# USB-Serial.net
KiCad netlist of a schematic drawn in Altium Designer
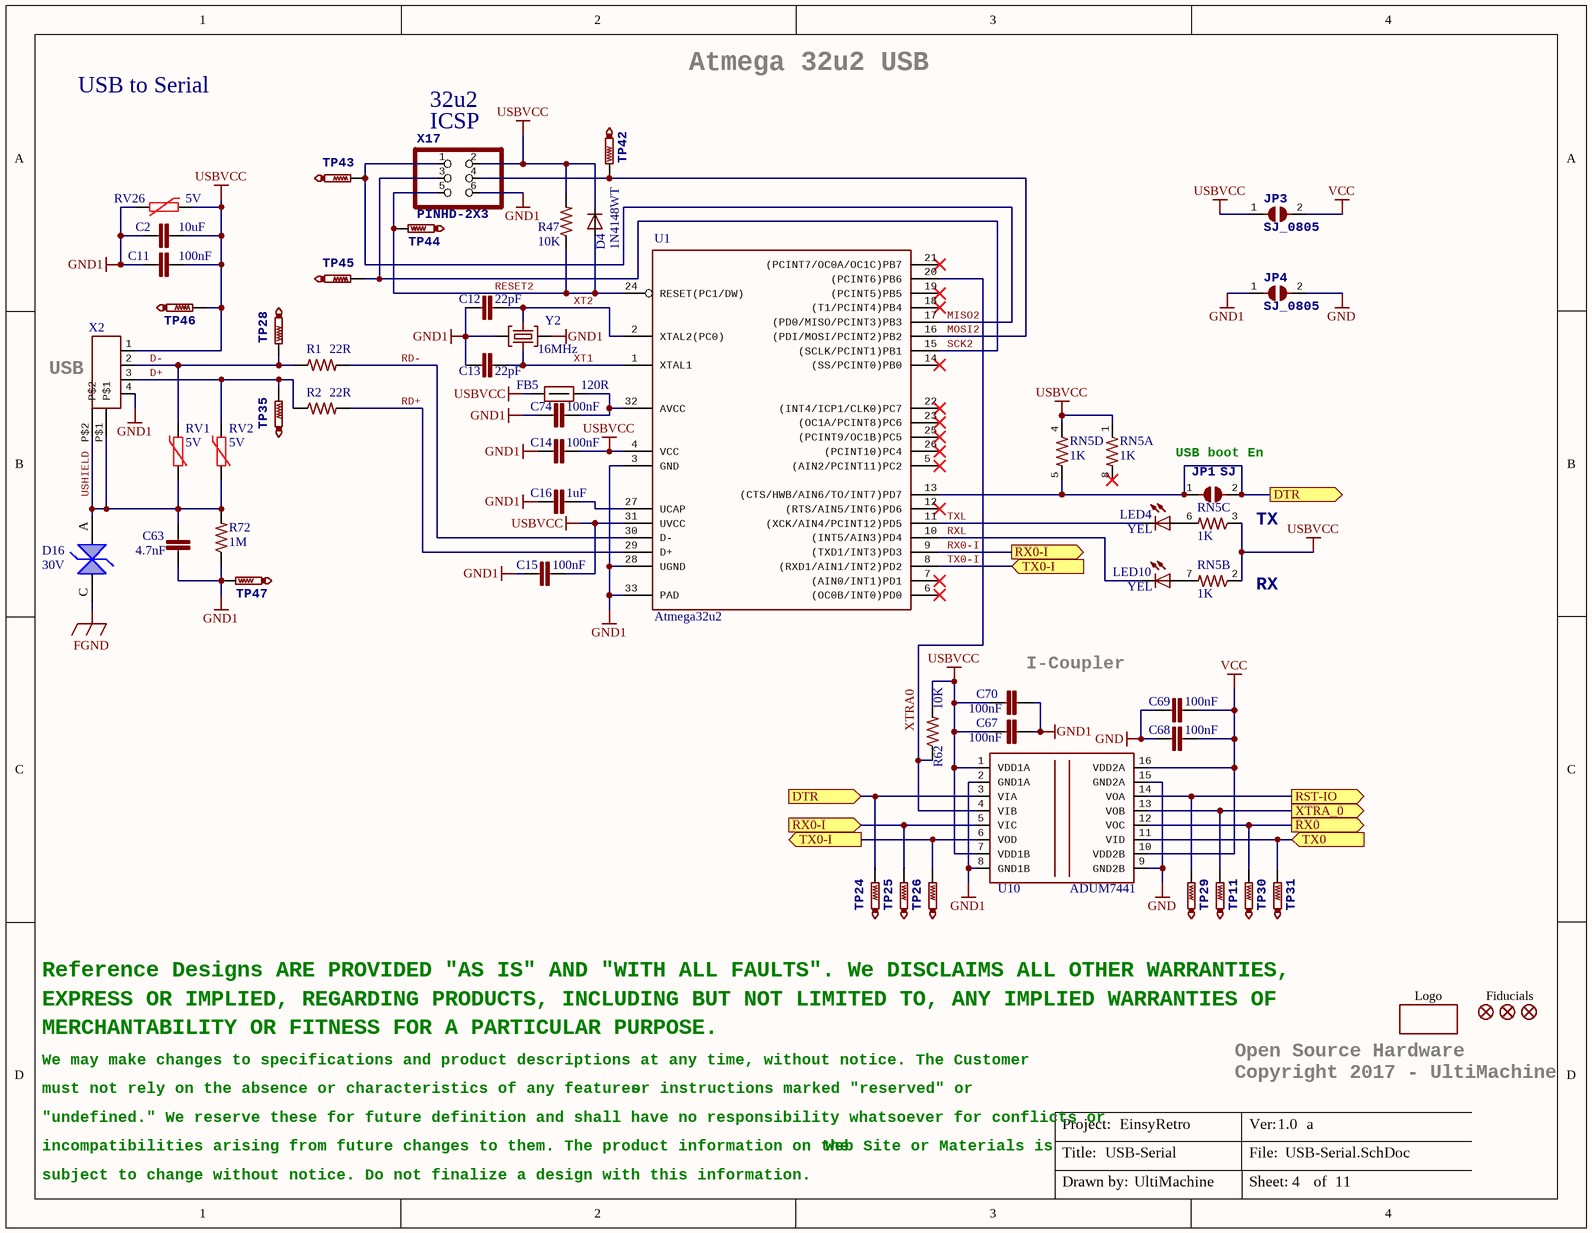
[diagram p0: USB-Serial.SchDoc]

(export (version "E")
  (design (tool "Eeschema 10.0.6"))
  (components
    (comp (ref "C2")
      (value "10uF")
      (footprint "C0805")
      (description "CAP CER 0805 10uF 10V 10% X5R")
      (fields (field (name "MANUFACTURER") "Kemet") (field (name "TOLERANCE") "+/- 10%"))
      (libsource (lib "3Delight") (part "C0805C106K8PACTU"))
    )
    (comp (ref "C11")
      (value "100nF")
      (footprint "C0402")
      (description "CAP CER 0402 100nF 16V 10% X7R")
      (fields (field (name "MANUFACTURER") "Murata") (field (name "TOLERANCE") "+/- 10%"))
      (libsource (lib "") (part "GRM155R71C104KA88D_1"))
    )
    (comp (ref "C12")
      (value "22pF")
      (footprint "C0402")
      (description "CAP CER 0402 22pF 50V 5% C0G")
      (fields (field (name "MANUFACTURER") "AVX") (field (name "PART") "22pF 50V"))
      (libsource (lib "3Delight") (part "04025A220JAT2A"))
    )
    (comp (ref "C13")
      (value "22pF")
      (footprint "C0402")
      (description "CAP CER 0402 22pF 50V 5% C0G")
      (fields (field (name "MANUFACTURER") "AVX") (field (name "PART") "22pF 50V"))
      (libsource (lib "3Delight") (part "04025A220JAT2A"))
    )
    (comp (ref "C14")
      (value "100nF")
      (footprint "C0402")
      (description "CAP CER 0402 100nF 16V 10% X7R")
      (fields (field (name "MANUFACTURER") "Murata") (field (name "TOLERANCE") "+/- 10%"))
      (libsource (lib "") (part "GRM155R71C104KA88D_1"))
    )
    (comp (ref "C15")
      (value "100nF")
      (footprint "C0402")
      (description "CAP CER 0402 100nF 16V 10% X7R")
      (fields (field (name "MANUFACTURER") "Murata") (field (name "TOLERANCE") "+/- 10%"))
      (libsource (lib "") (part "GRM155R71C104KA88D_1"))
    )
    (comp (ref "C16")
      (value "1uF")
      (footprint "C0402")
      (description "CAP CER 0402 1uF 6.3V 10% X5R")
      (fields (field (name "MANUFACTURER") "Murata") (field (name "TOLERANCE") "+/- 10%"))
      (libsource (lib "3Delight") (part "GRM155R60J105KE19D"))
    )
    (comp (ref "C63")
      (value "4.7nF")
      (footprint "C0402")
      (description "CAP CER 0402 4.7nF 25V 10% X7R")
      (fields (field (name "MANUFACTURER") "YAGEO") (field (name "TOLERANCE") "+/- 10%"))
      (libsource (lib "3Delight") (part "CC0402KRX7R8BB472"))
    )
    (comp (ref "C67")
      (value "100nF")
      (footprint "C0402")
      (description "CAP CER 0402 100nF 16V 10% X7R")
      (fields (field (name "MANUFACTURER") "Murata") (field (name "TOLERANCE") "+/- 10%"))
      (libsource (lib "") (part "GRM155R71C104KA88D_1"))
    )
    (comp (ref "C68")
      (value "100nF")
      (footprint "C0402")
      (description "CAP CER 0402 100nF 16V 10% X7R")
      (fields (field (name "MANUFACTURER") "Murata") (field (name "TOLERANCE") "+/- 10%"))
      (libsource (lib "3Delight") (part "GRM155R71C104KA88D"))
    )
    (comp (ref "C69")
      (value "100nF")
      (footprint "C0402")
      (description "CAP CER 0402 100nF 16V 10% X7R")
      (fields (field (name "MANUFACTURER") "Murata") (field (name "TOLERANCE") "+/- 10%"))
      (libsource (lib "") (part "GRM155R71C104KA88D_1"))
    )
    (comp (ref "C70")
      (value "100nF")
      (footprint "C0402")
      (description "CAP CER 0402 100nF 16V 10% X7R")
      (fields (field (name "MANUFACTURER") "Murata") (field (name "TOLERANCE") "+/- 10%"))
      (libsource (lib "3Delight") (part "GRM155R71C104KA88D"))
    )
    (comp (ref "C74")
      (value "100nF")
      (footprint "C0402")
      (description "CAP CER 0402 100nF 16V 10% X7R")
      (fields (field (name "MANUFACTURER") "Murata") (field (name "TOLERANCE") "+/- 10%"))
      (libsource (lib "") (part "GRM155R71C104KA88D_1"))
    )
    (comp (ref "D4")
      (value "1N4148WT")
      (footprint "SOD523")
      (description "DIODE SOD523")
      (fields (field (name "MANUFACTURER") "Fairchild") (field (name "TOLERANCE") "NA"))
      (libsource (lib "3Delight") (part "1N4148WT"))
    )
    (comp (ref "D16")
      (value "30V")
      (footprint "SOD323-R")
      (description "DIODE TVS")
      (fields (field (name "MANUFACTURER") "Rohm") (field (name "TOLERANCE") "NA"))
      (libsource (lib "3Delight") (part "RSB39VTE-17"))
    )
    (comp (ref "FB5")
      (value "120R")
      (footprint "FB0603")
      (description "FERRITE BEAD 120 OHM 0603 1LN")
      (fields (field (name "MANUFACTURER") "Samsung") (field (name "PART") "FERRITE 120R 3A 0603"))
      (libsource (lib "3Delight") (part "FERRITE 220R 2.5A 0603"))
    )
    (comp (ref "FID1")
      (value "FIDUCIAL")
      (footprint "FIDUCIAL-1X2")
      (description "Fiducial")
      (libsource (lib "3Delight") (part "FIDUCIAL"))
    )
    (comp (ref "FID2")
      (value "FIDUCIAL")
      (footprint "FIDUCIAL-1X2")
      (description "Fiducial")
      (libsource (lib "3Delight") (part "FIDUCIAL"))
    )
    (comp (ref "FID3")
      (value "FIDUCIAL")
      (footprint "FIDUCIAL-1X2")
      (description "Fiducial")
      (libsource (lib "3Delight") (part "FIDUCIAL"))
    )
    (comp (ref "JP1")
      (value "SJ")
      (footprint "SJ")
      (description "SMD solder jumper")
      (libsource (lib "3Delight") (part "SJ"))
    )
    (comp (ref "JP3")
      (value "SJ_0805")
      (footprint "R0805")
      (description "SMD solder jumper")
      (fields (field (name "PUBLISHER") "UltiMachine"))
      (libsource (lib "3Delight") (part "SJ_0805"))
    )
    (comp (ref "JP4")
      (value "SJ_0805")
      (footprint "R0805")
      (description "SMD solder jumper")
      (fields (field (name "PUBLISHER") "UltiMachine"))
      (libsource (lib "3Delight") (part "SJ_0805"))
    )
    (comp (ref "LED4")
      (value "YEL")
      (footprint "LED2012120")
      (description "LED 0805 Yellow")
      (fields (field (name "MANUFACTURER") "Dialight") (field (name "TOLERANCE") "NA"))
      (libsource (lib "3Delight") (part "5988140107F"))
    )
    (comp (ref "LED10")
      (value "YEL")
      (footprint "LED2012120")
      (description "LED 0805 Yellow")
      (fields (field (name "MANUFACTURER") "Dialight") (field (name "TOLERANCE") "NA"))
      (libsource (lib "3Delight") (part "5988140107F"))
    )
    (comp (ref "LOGO1")
      (value "OSHW_LOGO_8MILX0150-NT")
      (footprint "OSHW_8X150_NOTEXT")
      (libsource (lib "3Delight") (part "OSHW_LOGO_8MILX0150-NT"))
    )
    (comp (ref "R1")
      (value "22R")
      (footprint "R0402")
      (description "RES 0402 22r 62.5mW 1%")
      (fields (field (name "MANUFACTURER") "Yageo") (field (name "TOLERANCE") "+/- 1%"))
      (libsource (lib "3Delight") (part "RC0402FR-0722RL"))
    )
    (comp (ref "R2")
      (value "22R")
      (footprint "R0402")
      (description "RES 0402 22r 62.5mW 1%")
      (fields (field (name "MANUFACTURER") "Yageo") (field (name "TOLERANCE") "+/- 1%"))
      (libsource (lib "3Delight") (part "RC0402FR-0722RL"))
    )
    (comp (ref "R47")
      (value "10K")
      (footprint "R0402")
      (description "RES SMD 10K OHM 1% 1/16W 0402")
      (fields (field (name "MANUFACTURER") "Yageo") (field (name "PART") "10k 1% 0402"))
      (libsource (lib "3Delight") (part "RC0402FR-0710KP"))
    )
    (comp (ref "R62")
      (value "10K")
      (footprint "R0402")
      (description "RES SMD 10K OHM 1% 1/16W 0402")
      (fields (field (name "MANUFACTURER") "Yageo") (field (name "PART") "10k 1% 0402"))
      (libsource (lib "3Delight") (part "RC0402FR-0710KP"))
    )
    (comp (ref "R72")
      (value "1M")
      (footprint "R0402")
      (description "RES 0402 1M 100mW 5%")
      (fields (field (name "MANUFACTURER") "Panasonic") (field (name "TOLERANCE") "+/- 1%"))
      (libsource (lib "3Delight") (part "ERJ2GEJ105X"))
    )
    (comp (ref "RN5")
      (value "1K")
      (footprint "CAY16")
      (description "RES ARRAY 4 RES 1K 1206 62.5mW 5%")
      (fields (field (name "MANUFACTURER") "Bourns") (field (name "TOLERANCE") "+/- 5%"))
      (libsource (lib "3Delight") (part "CAY16-102J4LF"))
    )
    (comp (ref "RV1")
      (value "5V")
      (footprint "R0603")
      (description "VAR 0603 5V")
      (fields (field (name "MANUFACTURER") "YAGEO") (field (name "PART") "5VDC"))
      (libsource (lib "3Delight") (part "CG0603MLC-05E"))
    )
    (comp (ref "RV2")
      (value "5V")
      (footprint "R0603")
      (description "VAR 0603 5V")
      (fields (field (name "MANUFACTURER") "YAGEO") (field (name "PART") "5VDC"))
      (libsource (lib "3Delight") (part "CG0603MLC-05E"))
    )
    (comp (ref "RV26")
      (value "5V")
      (footprint "R0603")
      (description "VAR 0603 5V")
      (fields (field (name "MANUFACTURER") "YAGEO") (field (name "PART") "5VDC"))
      (libsource (lib "3Delight") (part "CG0603MLC-05E"))
    )
    (comp (ref "TP11")
      (value "TestPoint")
      (footprint "TP1-27")
      (description "Test Point")
      (libsource (lib "") (part "TestPoint_1"))
    )
    (comp (ref "TP24")
      (value "TestPoint")
      (footprint "TP1-27")
      (description "Test Point")
      (libsource (lib "") (part "TestPoint_1"))
    )
    (comp (ref "TP25")
      (value "TestPoint")
      (footprint "TP1-27")
      (description "Test Point")
      (libsource (lib "") (part "TestPoint_1"))
    )
    (comp (ref "TP26")
      (value "TestPoint")
      (footprint "TP1-27")
      (description "Test Point")
      (libsource (lib "") (part "TestPoint_1"))
    )
    (comp (ref "TP28")
      (value "TestPoint")
      (footprint "TP1-27")
      (description "Test Point")
      (libsource (lib "") (part "TestPoint_2"))
    )
    (comp (ref "TP29")
      (value "TestPoint")
      (footprint "TP1-27")
      (description "Test Point")
      (libsource (lib "") (part "TestPoint_1"))
    )
    (comp (ref "TP30")
      (value "TestPoint")
      (footprint "TP1-27")
      (description "Test Point")
      (libsource (lib "") (part "TestPoint_1"))
    )
    (comp (ref "TP31")
      (value "TestPoint")
      (footprint "TP1-27")
      (description "Test Point")
      (libsource (lib "") (part "TestPoint_1"))
    )
    (comp (ref "TP35")
      (value "TestPoint")
      (footprint "TP1-27")
      (description "Test Point")
      (libsource (lib "") (part "TestPoint_1"))
    )
    (comp (ref "TP42")
      (value "TestPoint")
      (footprint "TP1-27")
      (description "Test Point")
      (libsource (lib "") (part "TestPoint_2"))
    )
    (comp (ref "TP43")
      (value "TestPoint")
      (footprint "TP1-27")
      (description "Test Point")
      (libsource (lib "3Delight") (part "TestPoint"))
    )
    (comp (ref "TP44")
      (value "TestPoint")
      (footprint "TP1-27")
      (description "Test Point")
      (libsource (lib "") (part "TestPoint_3"))
    )
    (comp (ref "TP45")
      (value "TestPoint")
      (footprint "TP1-27")
      (description "Test Point")
      (libsource (lib "3Delight") (part "TestPoint"))
    )
    (comp (ref "TP46")
      (value "TestPoint")
      (footprint "TP1-27")
      (description "Test Point")
      (libsource (lib "3Delight") (part "TestPoint"))
    )
    (comp (ref "TP47")
      (value "TestPoint")
      (footprint "TP1-27")
      (description "Test Point")
      (libsource (lib "") (part "TestPoint_3"))
    )
    (comp (ref "U1")
      (value "Atmega32u2")
      (footprint "QFN32_050050")
      (fields
        (field (name "MANUFACTURER") "Microchip")
        (field (name "PART") "ATMEGA32U2")
        (field (name "TOLERANCE") "NA")
      )
      (libsource (lib "3Delight") (part "ATMEGA32U2-MU2"))
    )
    (comp (ref "U10")
      (value "ADUM7441")
      (footprint "QSOP16")
      (description "4ch iCoupler")
      (fields (field (name "MANUFACTURER") "Analog Devices") (field (name "PART") "ADUM7441ARQZ"))
      (libsource (lib "3Delight") (part "ADUM7441"))
    )
    (comp (ref "X2")
      (value "USB-B")
      (footprint "PN61729")
      (description "USB connector B PTH")
      (fields (field (name "MANUFACTURER") "FCI") (field (name "TOLERANCE") "NA"))
      (libsource (lib "3Delight") (part "USB-B"))
    )
    (comp (ref "X17")
      (value "PINHD-2X3")
      (footprint "2X03")
      (description "CONN HEADER VERT 6POS GOLD")
      (fields (field (name "MANUFACTURER") "MultiComp") (field (name "PART") "6PIN"))
      (libsource (lib "Connectors") (part "PINHD-2X3"))
    )
    (comp (ref "Y2")
      (value "16MHz")
      (footprint "CRYS320250")
      (description "Crystal 16mHz 10ppm 10pF")
      (fields (field (name "MANUFACTURER") "TXC") (field (name "TOLERANCE") "10ppm"))
      (libsource (lib "3Delight") (part "7M-16.000MEEQ-T"))
    )
  )
  (nets
    (net (code "1") (name "/D+") (class "Default")
      (node (ref "R2") (pin "1") (pinfunction "1_1") (pintype "passive"))
      (node (ref "RV2") (pin "2") (pinfunction "2_2") (pintype "passive"))
      (node (ref "TP35") (pin "TP") (pinfunction "TP_TP") (pintype "passive"))
      (node (ref "X2") (pin "3") (pinfunction "3_3") (pintype "passive"))
    )
    (net (code "2") (name "/D-") (class "Default")
      (node (ref "R1") (pin "1") (pinfunction "1_1") (pintype "passive"))
      (node (ref "RV1") (pin "2") (pinfunction "2_2") (pintype "passive"))
      (node (ref "TP28") (pin "TP") (pinfunction "TP_TP") (pintype "passive"))
      (node (ref "X2") (pin "2") (pinfunction "2_2") (pintype "passive"))
    )
    (net (code "3") (name "/DTR") (class "Default")
      (node (ref "JP1") (pin "1") (pinfunction "1_1") (pintype "passive"))
      (node (ref "JP1") (pin "2") (pinfunction "2_2") (pintype "passive"))
      (node (ref "RN5") (pin "5") (pinfunction "2_5") (pintype "passive"))
      (node (ref "TP24") (pin "TP") (pinfunction "TP_TP") (pintype "passive"))
      (node (ref "U1") (pin "13") (pinfunction "(CTS/HWB/AIN6/TO/INT7)PD7_13") (pintype "passive"))
      (node (ref "U10") (pin "3") (pinfunction "VIA_3") (pintype "passive"))
    )
    (net (code "4") (name "/MISO2") (class "Default")
      (node (ref "TP43") (pin "TP") (pinfunction "TP_TP") (pintype "passive"))
      (node (ref "U1") (pin "17") (pinfunction "(PD0/MISO/PCINT3)PB3_17") (pintype "passive"))
      (node (ref "X17") (pin "1") (pinfunction "1_1") (pintype "passive"))
    )
    (net (code "5") (name "/MOSI2") (class "Default")
      (node (ref "TP42") (pin "TP") (pinfunction "TP_TP") (pintype "passive"))
      (node (ref "U1") (pin "16") (pinfunction "(PDI/MOSI/PCINT2)PB2_16") (pintype "passive"))
      (node (ref "X17") (pin "4") (pinfunction "4_4") (pintype "passive"))
    )
    (net (code "6") (name "/RD+") (class "Default")
      (node (ref "R2") (pin "2") (pinfunction "2_2") (pintype "passive"))
      (node (ref "U1") (pin "29") (pinfunction "D+_29") (pintype "passive"))
    )
    (net (code "7") (name "/RD-") (class "Default")
      (node (ref "R1") (pin "2") (pinfunction "2_2") (pintype "passive"))
      (node (ref "U1") (pin "30") (pinfunction "D-_30") (pintype "passive"))
    )
    (net (code "8") (name "/RESET2") (class "Default")
      (node (ref "D4") (pin "A") (pinfunction "A_A") (pintype "passive"))
      (node (ref "R47") (pin "1") (pinfunction "1_1") (pintype "passive"))
      (node (ref "TP44") (pin "TP") (pinfunction "TP_TP") (pintype "passive"))
      (node (ref "U1") (pin "24") (pinfunction "RESET(PC1/DW)_24") (pintype "passive"))
      (node (ref "X17") (pin "5") (pinfunction "5_5") (pintype "passive"))
    )
    (net (code "9") (name "/RST-IO") (class "Default")
      (node (ref "TP29") (pin "TP") (pinfunction "TP_TP") (pintype "passive"))
      (node (ref "U10") (pin "14") (pinfunction "VOA_14") (pintype "passive"))
    )
    (net (code "10") (name "/RX0") (class "Default")
      (node (ref "TP30") (pin "TP") (pinfunction "TP_TP") (pintype "passive"))
      (node (ref "U10") (pin "12") (pinfunction "VOC_12") (pintype "passive"))
    )
    (net (code "11") (name "/RX0-I") (class "Default")
      (node (ref "TP25") (pin "TP") (pinfunction "TP_TP") (pintype "passive"))
      (node (ref "U1") (pin "9") (pinfunction "(TXD1/INT3)PD3_9") (pintype "passive"))
      (node (ref "U10") (pin "5") (pinfunction "VIC_5") (pintype "passive"))
    )
    (net (code "12") (name "/RXL") (class "Default")
      (node (ref "LED10") (pin "C") (pinfunction "C_C") (pintype "passive"))
      (node (ref "U1") (pin "10") (pinfunction "(INT5/AIN3)PD4_10") (pintype "passive"))
    )
    (net (code "13") (name "/SCK2") (class "Default")
      (node (ref "TP45") (pin "TP") (pinfunction "TP_TP") (pintype "passive"))
      (node (ref "U1") (pin "15") (pinfunction "(SCLK/PCINT1)PB1_15") (pintype "passive"))
      (node (ref "X17") (pin "3") (pinfunction "3_3") (pintype "passive"))
    )
    (net (code "14") (name "/TX0") (class "Default")
      (node (ref "TP31") (pin "TP") (pinfunction "TP_TP") (pintype "passive"))
      (node (ref "U10") (pin "11") (pinfunction "VID_11") (pintype "passive"))
    )
    (net (code "15") (name "/TX0-I") (class "Default")
      (node (ref "TP26") (pin "TP") (pinfunction "TP_TP") (pintype "passive"))
      (node (ref "U1") (pin "8") (pinfunction "(RXD1/AIN1/INT2)PD2_8") (pintype "passive"))
      (node (ref "U10") (pin "6") (pinfunction "VOD_6") (pintype "passive"))
    )
    (net (code "16") (name "/TXL") (class "Default")
      (node (ref "LED4") (pin "C") (pinfunction "C_C") (pintype "passive"))
      (node (ref "U1") (pin "11") (pinfunction "(XCK/AIN4/PCINT12)PD5_11") (pintype "passive"))
    )
    (net (code "17") (name "/USHIELD") (class "Default")
      (node (ref "C63") (pin "1") (pinfunction "1_1") (pintype "passive"))
      (node (ref "D16") (pin "A") (pinfunction "A_A") (pintype "power_in"))
      (node (ref "R72") (pin "2") (pinfunction "2_2") (pintype "passive"))
      (node (ref "RV1") (pin "1") (pinfunction "1_1") (pintype "passive"))
      (node (ref "RV2") (pin "1") (pinfunction "1_1") (pintype "passive"))
      (node (ref "X2") (pin "P$1") (pinfunction "P$1_P$1") (pintype "passive"))
      (node (ref "X2") (pin "P$2") (pinfunction "P$2_P$2") (pintype "passive"))
    )
    (net (code "18") (name "/XT1") (class "Default")
      (node (ref "C13") (pin "1") (pinfunction "1_1") (pintype "passive"))
      (node (ref "U1") (pin "1") (pinfunction "XTAL1_1") (pintype "passive"))
      (node (ref "Y2") (pin "1") (pinfunction "C1_1") (pintype "passive"))
    )
    (net (code "19") (name "/XT2") (class "Default")
      (node (ref "C12") (pin "1") (pinfunction "1_1") (pintype "passive"))
      (node (ref "U1") (pin "2") (pinfunction "XTAL2(PC0)_2") (pintype "passive"))
      (node (ref "Y2") (pin "3") (pinfunction "C2_3") (pintype "passive"))
    )
    (net (code "20") (name "/XTRA0") (class "Default")
      (node (ref "R62") (pin "1") (pinfunction "1_1") (pintype "passive"))
      (node (ref "U1") (pin "20") (pinfunction "(PCINT6)PB6_20") (pintype "passive"))
      (node (ref "U10") (pin "4") (pinfunction "VIB_4") (pintype "passive"))
    )
    (net (code "21") (name "/XTRA_0") (class "Default")
      (node (ref "TP11") (pin "TP") (pinfunction "TP_TP") (pintype "passive"))
      (node (ref "U10") (pin "13") (pinfunction "VOB_13") (pintype "passive"))
    )
    (net (code "22") (name "FGND") (class "Default")
      (node (ref "D16") (pin "C") (pinfunction "C_C") (pintype "power_in"))
    )
    (net (code "23") (name "GND") (class "Default")
      (node (ref "C68") (pin "1") (pinfunction "1_1") (pintype "passive"))
      (node (ref "C69") (pin "2") (pinfunction "2_2") (pintype "passive"))
      (node (ref "JP4") (pin "2") (pinfunction "2_2") (pintype "passive"))
      (node (ref "U10") (pin "15") (pinfunction "GND2A_15") (pintype "passive"))
      (node (ref "U10") (pin "9") (pinfunction "GND2B_9") (pintype "passive"))
    )
    (net (code "24") (name "GND1") (class "Default")
      (node (ref "C11") (pin "2") (pinfunction "2_2") (pintype "passive"))
      (node (ref "C12") (pin "2") (pinfunction "2_2") (pintype "passive"))
      (node (ref "C13") (pin "2") (pinfunction "2_2") (pintype "passive"))
      (node (ref "C14") (pin "2") (pinfunction "2_2") (pintype "passive"))
      (node (ref "C15") (pin "2") (pinfunction "2_2") (pintype "passive"))
      (node (ref "C16") (pin "2") (pinfunction "2_2") (pintype "passive"))
      (node (ref "C2") (pin "1") (pinfunction "1_1") (pintype "passive"))
      (node (ref "C63") (pin "2") (pinfunction "2_2") (pintype "passive"))
      (node (ref "C67") (pin "1") (pinfunction "1_1") (pintype "passive"))
      (node (ref "C70") (pin "2") (pinfunction "2_2") (pintype "passive"))
      (node (ref "C74") (pin "2") (pinfunction "2_2") (pintype "passive"))
      (node (ref "JP4") (pin "1") (pinfunction "1_1") (pintype "passive"))
      (node (ref "R72") (pin "1") (pinfunction "1_1") (pintype "passive"))
      (node (ref "RV26") (pin "1") (pinfunction "1_1") (pintype "passive"))
      (node (ref "TP47") (pin "TP") (pinfunction "TP_TP") (pintype "passive"))
      (node (ref "U1") (pin "28") (pinfunction "UGND_28") (pintype "power_in"))
      (node (ref "U1") (pin "3") (pinfunction "GND_3") (pintype "power_in"))
      (node (ref "U1") (pin "33") (pinfunction "PAD_33") (pintype "power_in"))
      (node (ref "U10") (pin "2") (pinfunction "GND1A_2") (pintype "passive"))
      (node (ref "U10") (pin "8") (pinfunction "GND1B_8") (pintype "passive"))
      (node (ref "X17") (pin "6") (pinfunction "6_6") (pintype "passive"))
      (node (ref "X2") (pin "4") (pinfunction "4_4") (pintype "passive"))
      (node (ref "Y2") (pin "2") (pinfunction "GND_2") (pintype "passive"))
      (node (ref "Y2") (pin "4") (pinfunction "GND_4") (pintype "passive"))
    )
    (net (code "25") (name "Net-(RN5B-2)") (class "Default")
      (node (ref "LED10") (pin "A") (pinfunction "A_A") (pintype "passive"))
      (node (ref "RN5") (pin "7") (pinfunction "2_7") (pintype "passive"))
    )
    (net (code "26") (name "Net-(RN5C-2)") (class "Default")
      (node (ref "LED4") (pin "A") (pinfunction "A_A") (pintype "passive"))
      (node (ref "RN5") (pin "6") (pinfunction "2_6") (pintype "passive"))
    )
    (net (code "27") (name "Net-(U1-AVCC)") (class "Default")
      (node (ref "C74") (pin "1") (pinfunction "1_1") (pintype "passive"))
      (node (ref "FB5") (pin "2") (pinfunction "2_2") (pintype "passive"))
      (node (ref "U1") (pin "32") (pinfunction "AVCC_32") (pintype "power_in"))
    )
    (net (code "28") (name "Net-(U1-UCAP)") (class "Default")
      (node (ref "C16") (pin "1") (pinfunction "1_1") (pintype "passive"))
      (node (ref "U1") (pin "27") (pinfunction "UCAP_27") (pintype "passive"))
    )
    (net (code "29") (name "USBVCC") (class "Default")
      (node (ref "C11") (pin "1") (pinfunction "1_1") (pintype "passive"))
      (node (ref "C14") (pin "1") (pinfunction "1_1") (pintype "passive"))
      (node (ref "C15") (pin "1") (pinfunction "1_1") (pintype "passive"))
      (node (ref "C2") (pin "2") (pinfunction "2_2") (pintype "passive"))
      (node (ref "C67") (pin "2") (pinfunction "2_2") (pintype "passive"))
      (node (ref "C70") (pin "1") (pinfunction "1_1") (pintype "passive"))
      (node (ref "D4") (pin "C") (pinfunction "C_C") (pintype "passive"))
      (node (ref "FB5") (pin "1") (pinfunction "1_1") (pintype "passive"))
      (node (ref "JP3") (pin "1") (pinfunction "1_1") (pintype "passive"))
      (node (ref "R47") (pin "2") (pinfunction "2_2") (pintype "passive"))
      (node (ref "R62") (pin "2") (pinfunction "2_2") (pintype "passive"))
      (node (ref "RN5") (pin "1") (pinfunction "1_1") (pintype "passive"))
      (node (ref "RN5") (pin "2") (pinfunction "1_2") (pintype "passive"))
      (node (ref "RN5") (pin "3") (pinfunction "1_3") (pintype "passive"))
      (node (ref "RN5") (pin "4") (pinfunction "1_4") (pintype "passive"))
      (node (ref "RV26") (pin "2") (pinfunction "2_2") (pintype "passive"))
      (node (ref "TP46") (pin "TP") (pinfunction "TP_TP") (pintype "passive"))
      (node (ref "U1") (pin "31") (pinfunction "UVCC_31") (pintype "power_in"))
      (node (ref "U1") (pin "4") (pinfunction "VCC_4") (pintype "power_in"))
      (node (ref "U10") (pin "1") (pinfunction "VDD1A_1") (pintype "passive"))
      (node (ref "U10") (pin "7") (pinfunction "VDD1B_7") (pintype "passive"))
      (node (ref "X17") (pin "2") (pinfunction "2_2") (pintype "passive"))
      (node (ref "X2") (pin "1") (pinfunction "1_1") (pintype "passive"))
    )
    (net (code "30") (name "VCC") (class "Default")
      (node (ref "C68") (pin "2") (pinfunction "2_2") (pintype "passive"))
      (node (ref "C69") (pin "1") (pinfunction "1_1") (pintype "passive"))
      (node (ref "JP3") (pin "2") (pinfunction "2_2") (pintype "passive"))
      (node (ref "U10") (pin "10") (pinfunction "VDD2B_10") (pintype "passive"))
      (node (ref "U10") (pin "16") (pinfunction "VDD2A_16") (pintype "passive"))
    )
    (net (code "31") (name "unconnected-(RN5A-2-Pad8)") (class "Default")
      (node (ref "RN5") (pin "8") (pinfunction "2_8") (pintype "passive+no_connect"))
    )
    (net (code "32") (name "unconnected-(U1-(AIN0{slash}INT1)PD1-Pad7)") (class "Default")
      (node (ref "U1") (pin "7") (pinfunction "(AIN0/INT1)PD1_7") (pintype "passive+no_connect"))
    )
    (net (code "33") (name "unconnected-(U1-(AIN2{slash}PCINT11)PC2-Pad5)") (class "Default")
      (node (ref "U1") (pin "5") (pinfunction "(AIN2/PCINT11)PC2_5") (pintype "passive+no_connect"))
    )
    (net (code "34") (name "unconnected-(U1-(INT4{slash}ICP1{slash}CLK0)PC7-Pad22)") (class "Default")
      (node (ref "U1") (pin "22") (pinfunction "(INT4/ICP1/CLK0)PC7_22") (pintype "passive+no_connect"))
    )
    (net (code "35") (name "unconnected-(U1-(OC0B{slash}INT0)PD0-Pad6)") (class "Default")
      (node (ref "U1") (pin "6") (pinfunction "(OC0B/INT0)PD0_6") (pintype "passive+no_connect"))
    )
    (net (code "36") (name "unconnected-(U1-(OC1A{slash}PCINT8)PC6-Pad23)") (class "Default")
      (node (ref "U1") (pin "23") (pinfunction "(OC1A/PCINT8)PC6_23") (pintype "passive+no_connect"))
    )
    (net (code "37") (name "unconnected-(U1-(PCINT5)PB5-Pad19)") (class "Default")
      (node (ref "U1") (pin "19") (pinfunction "(PCINT5)PB5_19") (pintype "passive+no_connect"))
    )
    (net (code "38") (name "unconnected-(U1-(PCINT7{slash}OC0A{slash}OC1C)PB7-Pad21)") (class "Default")
      (node (ref "U1") (pin "21") (pinfunction "(PCINT7/OC0A/OC1C)PB7_21") (pintype "passive+no_connect"))
    )
    (net (code "39") (name "unconnected-(U1-(PCINT9{slash}OC1B)PC5-Pad25)") (class "Default")
      (node (ref "U1") (pin "25") (pinfunction "(PCINT9/OC1B)PC5_25") (pintype "passive+no_connect"))
    )
    (net (code "40") (name "unconnected-(U1-(PCINT10)PC4-Pad26)") (class "Default")
      (node (ref "U1") (pin "26") (pinfunction "(PCINT10)PC4_26") (pintype "passive+no_connect"))
    )
    (net (code "41") (name "unconnected-(U1-(RTS{slash}AIN5{slash}INT6)PD6-Pad12)") (class "Default")
      (node (ref "U1") (pin "12") (pinfunction "(RTS/AIN5/INT6)PD6_12") (pintype "passive+no_connect"))
    )
    (net (code "42") (name "unconnected-(U1-(SS{slash}PCINT0)PB0-Pad14)") (class "Default")
      (node (ref "U1") (pin "14") (pinfunction "(SS/PCINT0)PB0_14") (pintype "passive+no_connect"))
    )
    (net (code "43") (name "unconnected-(U1-(T1{slash}PCINT4)PB4-Pad18)") (class "Default")
      (node (ref "U1") (pin "18") (pinfunction "(T1/PCINT4)PB4_18") (pintype "passive+no_connect"))
    )
  )
)
